# nanderror.net
KiCad netlist of a schematic drawn in EAGLE
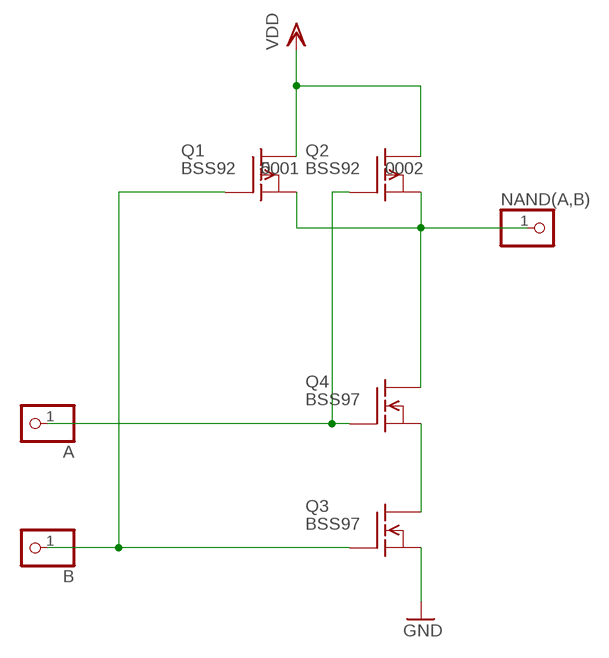
[diagram p0: schematic, sheet 1]

(export (version "E")
  (design (tool "Eeschema 10.0.6"))
  (components
    (comp (ref "A")
      (value "PINHD-1X1")
      (footprint "eagle-import:1X01")
      (libsource (lib "eagle-import") (part "PINHD-1X1"))
    )
    (comp (ref "B")
      (value "PINHD-1X1")
      (footprint "eagle-import:1X01")
      (libsource (lib "eagle-import") (part "PINHD-1X1"))
    )
    (comp (ref "NAND(A,B)")
      (value "PINHD-1X1")
      (footprint "eagle-import:1X01")
      (libsource (lib "eagle-import") (part "PINHD-1X1"))
    )
    (comp (ref "Q1")
      (value "BSS92")
      (footprint "eagle-import:TO92")
      (fields (field (name "P1") "0001") (field (name "TEST2") "5") (field (name "uid") "8"))
      (libsource (lib "eagle-import") (part "BSS92"))
    )
    (comp (ref "Q2")
      (value "BSS92")
      (footprint "eagle-import:TO92")
      (fields (field (name "P2") "0002"))
      (libsource (lib "eagle-import") (part "BSS92"))
    )
    (comp (ref "Q3")
      (value "BSS97")
      (footprint "eagle-import:TO202")
      (libsource (lib "eagle-import") (part "BSS97"))
    )
    (comp (ref "Q4")
      (value "BSS97")
      (footprint "eagle-import:TO202")
      (libsource (lib "eagle-import") (part "BSS97"))
    )
  )
  (nets
    (net (code "1") (name "GND") (class "Default")
      (node (ref "Q3") (pin "1") (pinfunction "S_1") (pintype "passive"))
    )
    (net (code "2") (name "Net-(Q1-G)") (class "Default")
      (node (ref "B") (pin "1") (pinfunction "1_1") (pintype "passive"))
      (node (ref "Q1") (pin "1") (pinfunction "G_1") (pintype "passive"))
      (node (ref "Q3") (pin "3") (pinfunction "G_3") (pintype "passive"))
    )
    (net (code "3") (name "Net-(Q1-S)") (class "Default")
      (node (ref "NAND(A,B)") (pin "1") (pinfunction "1_1") (pintype "passive"))
      (node (ref "Q1") (pin "3") (pinfunction "S_3") (pintype "passive"))
      (node (ref "Q2") (pin "3") (pinfunction "S_3") (pintype "passive"))
      (node (ref "Q4") (pin "2") (pinfunction "D_2") (pintype "passive"))
    )
    (net (code "4") (name "Net-(Q2-G)") (class "Default")
      (node (ref "A") (pin "1") (pinfunction "1_1") (pintype "passive"))
      (node (ref "Q2") (pin "1") (pinfunction "G_1") (pintype "passive"))
      (node (ref "Q4") (pin "3") (pinfunction "G_3") (pintype "passive"))
    )
    (net (code "5") (name "Net-(Q3-D)") (class "Default")
      (node (ref "Q3") (pin "2") (pinfunction "D_2") (pintype "passive"))
      (node (ref "Q4") (pin "1") (pinfunction "S_1") (pintype "passive"))
    )
    (net (code "6") (name "VDD") (class "Default")
      (node (ref "Q1") (pin "2") (pinfunction "D_2") (pintype "passive"))
      (node (ref "Q2") (pin "2") (pinfunction "D_2") (pintype "passive"))
    )
  )
)
